# enable.net
KiCad netlist of a schematic drawn in EAGLE
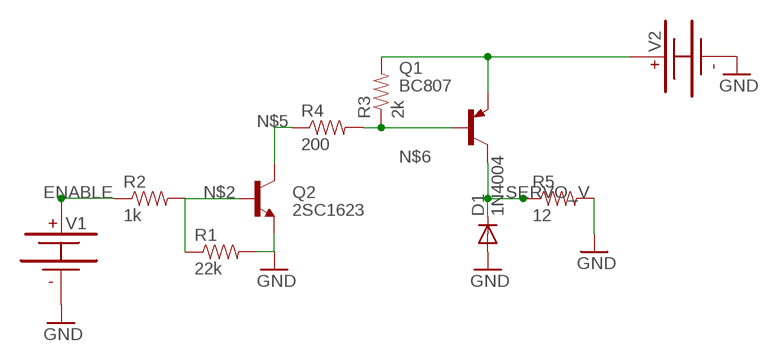
[diagram p0: schematic, sheet 1]

(export (version "E")
  (design (tool "Eeschema 10.0.6"))
  (components
    (comp (ref "D1")
      (value "1N4004")
      (footprint "eagle-import:DIODE_C221B1A")
      (libsource (lib "eagle-import") (part "DIODE_DIODE-C221B1A"))
    )
    (comp (ref "Q1")
      (value "BC807")
      (footprint "eagle-import:SOT23-BCE")
      (libsource (lib "eagle-import") (part "-PNP-SOT23-BCE"))
    )
    (comp (ref "Q2")
      (value "2SC1623")
      (footprint "eagle-import:SOT23")
      (libsource (lib "eagle-import") (part "TRANSISTOR_NPNSOT23"))
    )
    (comp (ref "R1")
      (value "22k")
      (footprint "eagle-import:0603-RES")
      (libsource (lib "eagle-import") (part "RESISTOR0603-RES"))
    )
    (comp (ref "R2")
      (value "1k")
      (footprint "eagle-import:0603-RES")
      (libsource (lib "eagle-import") (part "RESISTOR0603-RES"))
    )
    (comp (ref "R3")
      (value "2k")
      (footprint "eagle-import:0603-RES")
      (libsource (lib "eagle-import") (part "RESISTOR0603-RES"))
    )
    (comp (ref "R4")
      (value "200")
      (footprint "eagle-import:0603-RES")
      (libsource (lib "eagle-import") (part "RESISTOR0603-RES"))
    )
    (comp (ref "R5")
      (value "12")
      (footprint "eagle-import:0603-RES")
      (libsource (lib "eagle-import") (part "RESISTOR0603-RES"))
    )
    (comp (ref "V1")
      (value "VSOURCE")
      (footprint "eagle-import:VSOURCE")
      (libsource (lib "eagle-import") (part "VSOURCE"))
    )
    (comp (ref "V2")
      (value "VSOURCE")
      (footprint "eagle-import:VSOURCE")
      (libsource (lib "eagle-import") (part "VSOURCE"))
    )
  )
  (nets
    (net (code "1") (name "/ENABLE") (class "Default")
      (node (ref "R2") (pin "1") (pinfunction "1_1") (pintype "passive"))
      (node (ref "V1") (pin "1") (pinfunction "1_1") (pintype "output"))
    )
    (net (code "2") (name "/N$2") (class "Default")
      (node (ref "Q2") (pin "1") (pinfunction "B_1") (pintype "passive"))
      (node (ref "R1") (pin "1") (pinfunction "1_1") (pintype "passive"))
      (node (ref "R2") (pin "2") (pinfunction "2_2") (pintype "passive"))
    )
    (net (code "3") (name "/N$5") (class "Default")
      (node (ref "Q2") (pin "3") (pinfunction "C_3") (pintype "passive"))
      (node (ref "R4") (pin "1") (pinfunction "1_1") (pintype "passive"))
    )
    (net (code "4") (name "/N$6") (class "Default")
      (node (ref "Q1") (pin "B") (pinfunction "B_B") (pintype "passive"))
      (node (ref "R3") (pin "1") (pinfunction "1_1") (pintype "passive"))
      (node (ref "R4") (pin "2") (pinfunction "2_2") (pintype "passive"))
    )
    (net (code "5") (name "/SERVO_V") (class "Default")
      (node (ref "D1") (pin "C") (pinfunction "C_C") (pintype "passive"))
      (node (ref "Q1") (pin "C") (pinfunction "C_C") (pintype "passive"))
      (node (ref "R5") (pin "1") (pinfunction "1_1") (pintype "passive"))
    )
    (net (code "6") (name "GND") (class "Default")
      (node (ref "D1") (pin "A") (pinfunction "A_A") (pintype "passive"))
      (node (ref "Q2") (pin "2") (pinfunction "E_2") (pintype "passive"))
      (node (ref "R1") (pin "2") (pinfunction "2_2") (pintype "passive"))
      (node (ref "R5") (pin "2") (pinfunction "2_2") (pintype "passive"))
      (node (ref "V1") (pin "2") (pinfunction "2_2") (pintype "output"))
      (node (ref "V2") (pin "2") (pinfunction "2_2") (pintype "output"))
    )
    (net (code "7") (name "Net-(Q1-PadE)") (class "Default")
      (node (ref "Q1") (pin "E") (pinfunction "E_E") (pintype "passive"))
      (node (ref "R3") (pin "2") (pinfunction "2_2") (pintype "passive"))
      (node (ref "V2") (pin "1") (pinfunction "1_1") (pintype "output"))
    )
  )
)
